# Light_Sensor_Node.net
KiCad netlist of a schematic drawn in Altium Designer
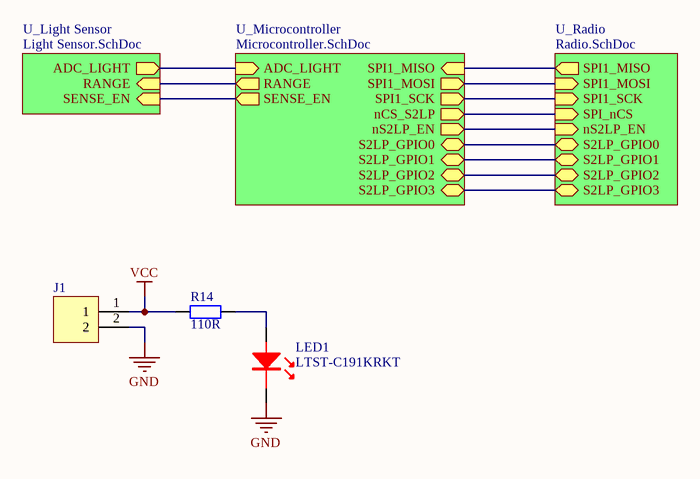
[diagram p0: Light Sensor Node.SchDoc]

(export (version "E")
  (design (tool "Eeschema 10.0.6"))
  (components
    (comp (ref "J1")
      (value "22-05-3021")
      (footprint "MOLEX_22-05-3021")
      (fields (field (name "MANUFACTURER") "Molex"))
      (libsource (lib "Light Sensor Node") (part "2WAY"))
    )
    (comp (ref "LED1")
      (value "LTST-C191KRKT")
      (footprint "LITEON_LTST-C191KRKT")
      (fields (field (name "MANUFACTURER") "Lite On"))
      (libsource (lib "Light Sensor Node") (part "LED_Red"))
    )
    (comp (ref "R14")
      (value "110R")
      (footprint "R0603")
      (description "RES")
      (fields
        (field (name "MANUFACTURER") "Yageo")
        (field (name "MANUFACTURER PART NUMBER") "RC0603FR-07110RL")
      )
      (libsource (lib "Light Sensor Node") (part "RES"))
    )
  )
  (nets
    (net (code "13") (name "GND") (class "Default")
      (node (ref "J1") (pin "2") (pinfunction "2_2") (pintype "passive"))
      (node (ref "LED1") (pin "K") (pinfunction "K_K") (pintype "passive"))
    )
    (net (code "14") (name "Net-(LED1-PadA)") (class "Default")
      (node (ref "LED1") (pin "A") (pinfunction "A_A") (pintype "passive"))
      (node (ref "R14") (pin "2") (pinfunction "2_2") (pintype "passive"))
    )
    (net (code "15") (name "VCC") (class "Default")
      (node (ref "J1") (pin "1") (pinfunction "1_1") (pintype "passive"))
      (node (ref "R14") (pin "1") (pinfunction "1_1") (pintype "passive"))
    )
  )
)
